# Version1.net
KiCad netlist of a schematic drawn in EAGLE
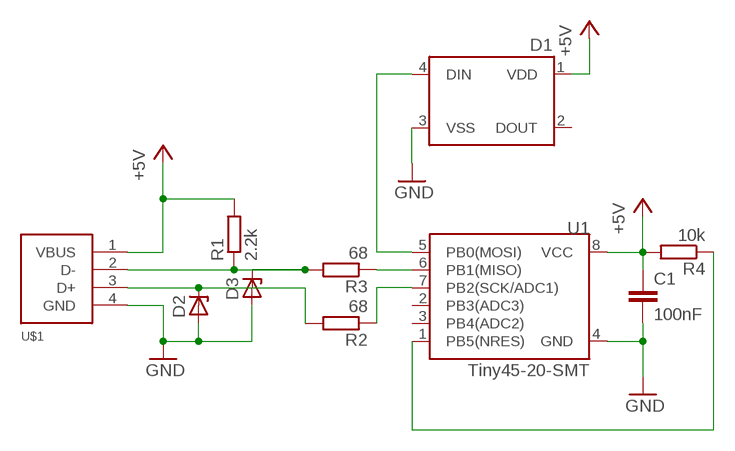
[diagram p0: schematic, sheet 1]

(export (version "E")
  (design (tool "Eeschema 10.0.6"))
  (components
    (comp (ref "C1")
      (value "100nF")
      (footprint "eagle-import:C0603")
      (libsource (lib "eagle-import") (part "C-EUC0603"))
    )
    (comp (ref "D1")
      (value "WS2812B")
      (footprint "eagle-import:WS2812B")
      (libsource (lib "eagle-import") (part "WS2812B"))
    )
    (comp (ref "D2")
      (value "ZENER-DIODESOD80C")
      (footprint "eagle-import:SOD80C")
      (libsource (lib "eagle-import") (part "ZENER-DIODESOD80C"))
    )
    (comp (ref "D3")
      (value "ZENER-DIODESOD80C")
      (footprint "eagle-import:SOD80C")
      (libsource (lib "eagle-import") (part "ZENER-DIODESOD80C"))
    )
    (comp (ref "R1")
      (value "2.2k")
      (footprint "eagle-import:R0603")
      (libsource (lib "eagle-import") (part "R-EU_R0603"))
    )
    (comp (ref "R2")
      (value "68")
      (footprint "eagle-import:R0603")
      (libsource (lib "eagle-import") (part "R-EU_R0603"))
    )
    (comp (ref "R3")
      (value "68")
      (footprint "eagle-import:R0603")
      (libsource (lib "eagle-import") (part "R-EU_R0603"))
    )
    (comp (ref "R4")
      (value "10k")
      (footprint "eagle-import:R0603")
      (libsource (lib "eagle-import") (part "R-EU_R0603"))
    )
    (comp (ref "U$1")
      (value "USB-CON-4PIN")
      (footprint "eagle-import:USB-MALE-A-PCB")
      (libsource (lib "eagle-import") (part "USB-CON-4PIN"))
    )
    (comp (ref "U1")
      (value "Tiny45-20-SMT")
      (footprint "eagle-import:SO08-EIAJ")
      (libsource (lib "eagle-import") (part "ATTINY45TINY45-20-SMT"))
    )
  )
  (nets
    (net (code "1") (name "+5V") (class "Default")
      (node (ref "C1") (pin "1") (pinfunction "1_1") (pintype "passive"))
      (node (ref "D1") (pin "1") (pinfunction "VDD_1") (pintype "power_in"))
      (node (ref "R1") (pin "2") (pinfunction "2_2") (pintype "passive"))
      (node (ref "R4") (pin "2") (pinfunction "2_2") (pintype "passive"))
      (node (ref "U$1") (pin "1") (pinfunction "VBUS_1") (pintype "power_in"))
      (node (ref "U1") (pin "8") (pinfunction "VCC_8") (pintype "bidirectional"))
    )
    (net (code "2") (name "GND") (class "Default")
      (node (ref "C1") (pin "2") (pinfunction "2_2") (pintype "passive"))
      (node (ref "D1") (pin "3") (pinfunction "VSS_3") (pintype "power_in"))
      (node (ref "D2") (pin "A") (pinfunction "A_A") (pintype "passive"))
      (node (ref "D3") (pin "A") (pinfunction "A_A") (pintype "passive"))
      (node (ref "U$1") (pin "4") (pinfunction "GND_4") (pintype "power_in"))
      (node (ref "U1") (pin "4") (pinfunction "GND_4") (pintype "bidirectional"))
    )
    (net (code "3") (name "Net-(D1-DIN)") (class "Default")
      (node (ref "D1") (pin "4") (pinfunction "DIN_4") (pintype "input"))
      (node (ref "U1") (pin "5") (pinfunction "PB0(MOSI)_5") (pintype "bidirectional"))
    )
    (net (code "4") (name "Net-(U$1-D+)") (class "Default")
      (node (ref "D2") (pin "C") (pinfunction "C_C") (pintype "passive"))
      (node (ref "R2") (pin "2") (pinfunction "2_2") (pintype "passive"))
      (node (ref "U$1") (pin "3") (pinfunction "D+_3") (pintype "bidirectional"))
    )
    (net (code "5") (name "Net-(U$1-D-)") (class "Default")
      (node (ref "D3") (pin "C") (pinfunction "C_C") (pintype "passive"))
      (node (ref "R1") (pin "1") (pinfunction "1_1") (pintype "passive"))
      (node (ref "R3") (pin "2") (pinfunction "2_2") (pintype "passive"))
      (node (ref "U$1") (pin "2") (pinfunction "D-_2") (pintype "bidirectional"))
    )
    (net (code "6") (name "Net-(U1-PB1(MISO))") (class "Default")
      (node (ref "R3") (pin "1") (pinfunction "1_1") (pintype "passive"))
      (node (ref "U1") (pin "6") (pinfunction "PB1(MISO)_6") (pintype "bidirectional"))
    )
    (net (code "7") (name "Net-(U1-PB2(SCK{slash}ADC1))") (class "Default")
      (node (ref "R2") (pin "1") (pinfunction "1_1") (pintype "passive"))
      (node (ref "U1") (pin "7") (pinfunction "PB2(SCK/ADC1)_7") (pintype "bidirectional"))
    )
    (net (code "8") (name "Net-(U1-PB5(NRES))") (class "Default")
      (node (ref "R4") (pin "1") (pinfunction "1_1") (pintype "passive"))
      (node (ref "U1") (pin "1") (pinfunction "PB5(NRES)_1") (pintype "bidirectional"))
    )
    (net (code "9") (name "unconnected-(D1-DOUT-Pad2)") (class "Default")
      (node (ref "D1") (pin "2") (pinfunction "DOUT_2") (pintype "output"))
    )
    (net (code "10") (name "unconnected-(U1-PB3(ADC3)-Pad2)") (class "Default")
      (node (ref "U1") (pin "2") (pinfunction "PB3(ADC3)_2") (pintype "bidirectional"))
    )
    (net (code "11") (name "unconnected-(U1-PB4(ADC2)-Pad3)") (class "Default")
      (node (ref "U1") (pin "3") (pinfunction "PB4(ADC2)_3") (pintype "bidirectional"))
    )
  )
)
